# Sheet2.net
KiCad netlist of a schematic drawn in Altium Designer
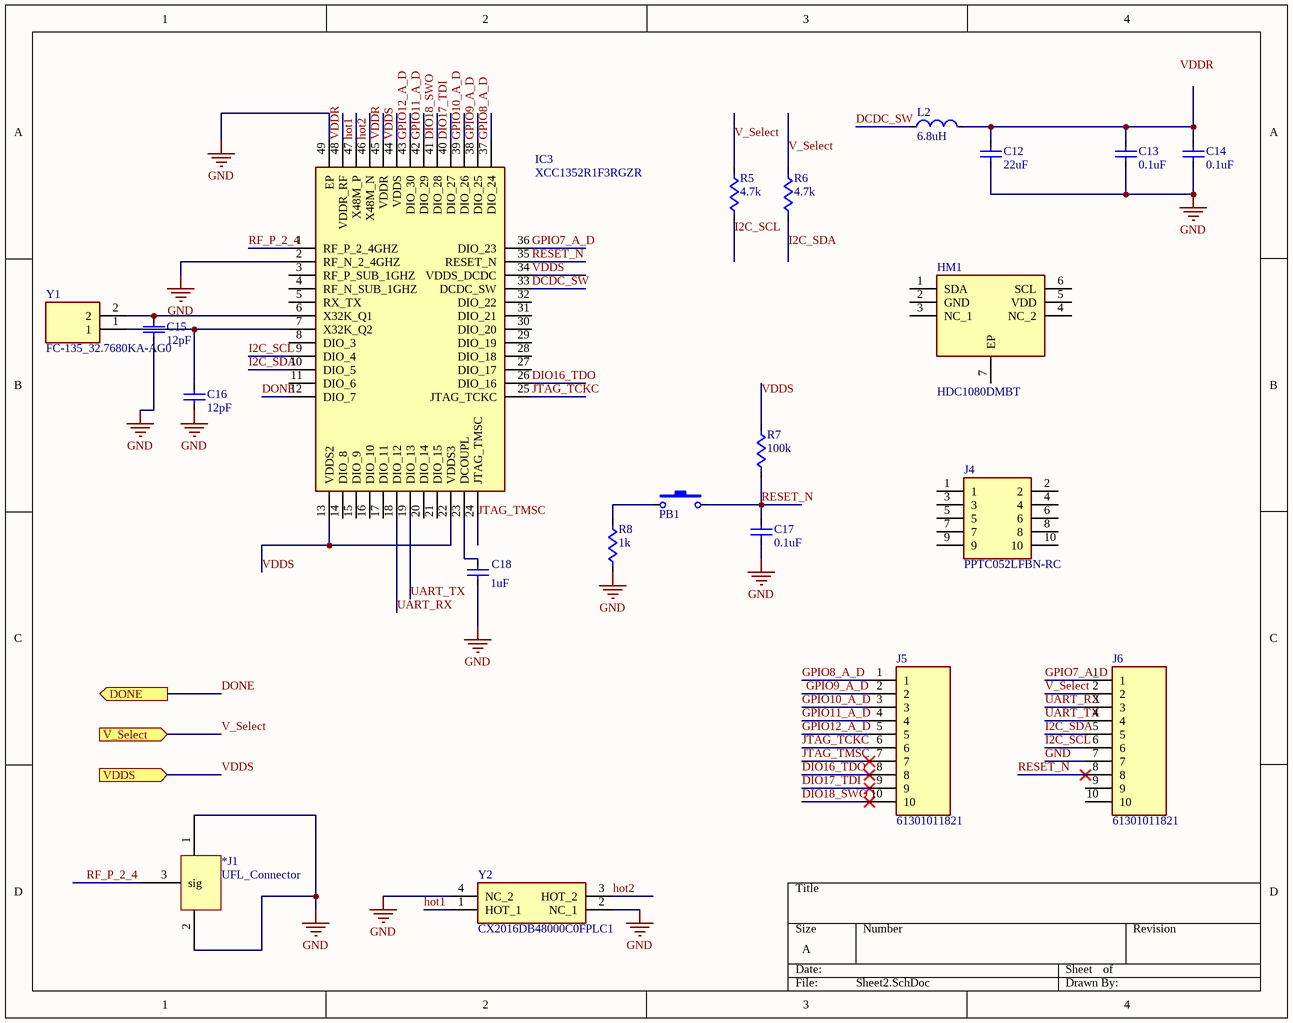
[diagram p0: Sheet2.SchDoc]

(export (version "E")
  (design (tool "Eeschema 10.0.6"))
  (components
    (comp (ref "*J1")
      (value "UFL_Connector")
      (footprint "UFL_Connector")
      (description "CONN U.FL RCPT STR 50 OHM SMD")
      (libsource (lib "Enviornmental_Sensor") (part "UFL_Connector"))
    )
    (comp (ref "C12")
      (value "22uF")
      (footprint "PASSIVE-CAPACITOR-0603")
      (description "Generic Capacitor")
      (libsource (lib "") (part "Passive-Capacitor (Generic)_1"))
    )
    (comp (ref "C13")
      (value "0.1uF")
      (footprint "PASSIVE-CAPACITOR-0603")
      (description "Generic Capacitor")
      (fields (field (name "Comment") "Passive-Capacitor (Generic)"))
      (libsource (lib "MasterLib") (part "Passive-Capacitor (Generic)"))
    )
    (comp (ref "C14")
      (value "0.1uF")
      (footprint "PASSIVE-CAPACITOR-0603")
      (description "Generic Capacitor")
      (fields (field (name "Comment") "Passive-Capacitor (Generic)"))
      (libsource (lib "MasterLib") (part "Passive-Capacitor (Generic)"))
    )
    (comp (ref "C15")
      (value "12pF")
      (footprint "PASSIVE-CAPACITOR-0603")
      (description "Generic Capacitor")
      (fields (field (name "Comment") "Passive-Capacitor (Generic)"))
      (libsource (lib "MasterLib") (part "Passive-Capacitor (Generic)"))
    )
    (comp (ref "C16")
      (value "12pF")
      (footprint "PASSIVE-CAPACITOR-0603")
      (description "Generic Capacitor")
      (fields (field (name "Comment") "Passive-Capacitor (Generic)"))
      (libsource (lib "MasterLib") (part "Passive-Capacitor (Generic)"))
    )
    (comp (ref "C17")
      (value "0.1uF")
      (footprint "PASSIVE-CAPACITOR-0603")
      (description "Generic Capacitor")
      (fields (field (name "Comment") "Passive-Capacitor (Generic)"))
      (libsource (lib "MasterLib") (part "Passive-Capacitor (Generic)"))
    )
    (comp (ref "C18")
      (value "1uF")
      (footprint "PASSIVE-CAPACITOR-0603")
      (description "Generic Capacitor")
      (fields (field (name "Comment") "Passive-Capacitor (Generic)"))
      (libsource (lib "MasterLib") (part "Passive-Capacitor (Generic)"))
    )
    (comp (ref "HM1")
      (value "HDC1080DMBT")
      (footprint "SON100P300X300X80-7N")
      (description "Hygrometer")
      (fields
        (field (name "MOUSER PART NUMBER") "595-HDC1080DMBT")
        (field (name "RS PART NUMBER") "1330170P")
      )
      (libsource (lib "Enviornmental_Sensor") (part "HDC1080DMBT"))
    )
    (comp (ref "IC3")
      (value "XCC1352R1F3RGZR")
      (footprint "QFN50P700X700X100-49N-D")
      (description "Integrated Circuit")
      (libsource (lib "Enviornmental_Sensor") (part "XCC1352R1F3RGZR"))
    )
    (comp (ref "J4")
      (value "PPTC052LFBN-RC")
      (footprint "SHDR10W87P254_2X5_1320X508X870P")
      (description "Connector")
      (libsource (lib "Enviornmental_Sensor") (part "PPTC052LFBN-RC"))
    )
    (comp (ref "J5")
      (value "61301011821")
      (footprint "SHDR10W87P0X254_1X10_2590X250X865P")
      (description "Connector")
      (fields (field (name "MOUSER PART NUMBER") "710-61301011821"))
      (libsource (lib "Enviornmental_Sensor") (part "61301011821"))
    )
    (comp (ref "J6")
      (value "61301011821")
      (footprint "SHDR10W87P0X254_1X10_2590X250X865P")
      (description "Connector")
      (fields (field (name "MOUSER PART NUMBER") "710-61301011821"))
      (libsource (lib "Enviornmental_Sensor") (part "61301011821"))
    )
    (comp (ref "L2")
      (value "6.8uH")
      (footprint "PASSIVE-INDUCTOR-0603")
      (description "Generic Inductor")
      (fields (field (name "Comment") "Passive-Inductor (Generic)"))
      (libsource (lib "MasterLib") (part "Passive-Inductor (Generic)"))
    )
    (comp (ref "PB1")
      (value "Interface-Push-Button")
      (footprint "INTERFACE-PUSH-BUTTON")
      (description "2.5mm Tall, 2.5N Force, Straight, SMD, Push Button")
      (fields
        (field (name "MANUFACTURER") "C&K Components")
        (field (name "MANUFACTURER PART NUMBER") "PTS820 J25K SMTR LFS")
      )
      (libsource (lib "MasterLib") (part "Interface-Push-Button"))
    )
    (comp (ref "R5")
      (value "4.7k")
      (footprint "PASSIVE-RESISTOR-0603")
      (description "Generic Resistor")
      (fields (field (name "Comment") "Passive-Resistor (Generic)"))
      (libsource (lib "MasterLib") (part "Passive-Resistor (Generic)"))
    )
    (comp (ref "R6")
      (value "4.7k")
      (footprint "PASSIVE-RESISTOR-0603")
      (description "Generic Resistor")
      (fields (field (name "Comment") "Passive-Resistor (Generic)"))
      (libsource (lib "MasterLib") (part "Passive-Resistor (Generic)"))
    )
    (comp (ref "R7")
      (value "100k")
      (footprint "PASSIVE-RESISTOR-0603")
      (description "Generic Resistor")
      (fields (field (name "Comment") "Passive-Resistor (Generic)"))
      (libsource (lib "MasterLib") (part "Passive-Resistor (Generic)"))
    )
    (comp (ref "R8")
      (value "1k")
      (footprint "PASSIVE-RESISTOR-0603")
      (description "Generic Resistor")
      (fields (field (name "Comment") "Passive-Resistor (Generic)"))
      (libsource (lib "MasterLib") (part "Passive-Resistor (Generic)"))
    )
    (comp (ref "Y1")
      (value "FC-135_32.7680KA-AG0")
      (footprint "FC135327680KAAG0")
      (description "Crystal or Oscillator")
      (fields
        (field (name "MANUFACTURER_PART_NUMBER") "FC-135 32.7680KA-AG0")
        (field (name "MOUSER PART NUMBER") "732-FC135-32.76KAAG0")
      )
      (libsource (lib "Enviornmental_Sensor") (part "FC-135_32.7680KA-AG0"))
    )
    (comp (ref "Y2")
      (value "CX2016DB48000C0FPLC1")
      (footprint "CX2016DB48000C0FPLC1")
      (description "Crystal or Oscillator")
      (fields (field (name "MOUSER PART NUMBER") "581-CX2016DB48CFPLC1"))
      (libsource (lib "Enviornmental_Sensor") (part "CX2016DB48000C0FPLC1"))
    )
  )
  (nets
    (net (code "1") (name "/DCDC_SW") (class "Default")
      (node (ref "IC3") (pin "33") (pinfunction "DCDC_SW_33") (pintype "passive"))
      (node (ref "L2") (pin "1") (pinfunction "1_1") (pintype "passive"))
    )
    (net (code "2") (name "/DIO16_TDO") (class "Default")
      (node (ref "IC3") (pin "26") (pinfunction "DIO_16_26") (pintype "passive"))
      (node (ref "J5") (pin "8") (pinfunction "8_8") (pintype "passive"))
    )
    (net (code "3") (name "/DIO17_TDI") (class "Default")
      (node (ref "IC3") (pin "40") (pinfunction "DIO_27_40") (pintype "passive"))
      (node (ref "J5") (pin "9") (pinfunction "9_9") (pintype "passive"))
    )
    (net (code "4") (name "/DIO18_SWO") (class "Default")
      (node (ref "IC3") (pin "41") (pinfunction "DIO_28_41") (pintype "passive"))
      (node (ref "J5") (pin "10") (pinfunction "10_10") (pintype "passive"))
    )
    (net (code "5") (name "/DONE") (class "Default")
      (node (ref "IC3") (pin "12") (pinfunction "DIO_7_12") (pintype "passive"))
    )
    (net (code "6") (name "/GPIO7_A_D") (class "Default")
      (node (ref "IC3") (pin "36") (pinfunction "DIO_23_36") (pintype "passive"))
      (node (ref "J6") (pin "1") (pinfunction "1_1") (pintype "passive"))
    )
    (net (code "7") (name "/GPIO8_A_D") (class "Default")
      (node (ref "IC3") (pin "37") (pinfunction "DIO_24_37") (pintype "passive"))
      (node (ref "J5") (pin "1") (pinfunction "1_1") (pintype "passive"))
    )
    (net (code "8") (name "/GPIO9_A_D") (class "Default")
      (node (ref "IC3") (pin "38") (pinfunction "DIO_25_38") (pintype "passive"))
      (node (ref "J5") (pin "2") (pinfunction "2_2") (pintype "passive"))
    )
    (net (code "9") (name "/GPIO10_A_D") (class "Default")
      (node (ref "IC3") (pin "39") (pinfunction "DIO_26_39") (pintype "passive"))
      (node (ref "J5") (pin "3") (pinfunction "3_3") (pintype "passive"))
    )
    (net (code "10") (name "/GPIO11_A_D") (class "Default")
      (node (ref "IC3") (pin "42") (pinfunction "DIO_29_42") (pintype "passive"))
      (node (ref "J5") (pin "4") (pinfunction "4_4") (pintype "passive"))
    )
    (net (code "11") (name "/GPIO12_A_D") (class "Default")
      (node (ref "IC3") (pin "43") (pinfunction "DIO_30_43") (pintype "passive"))
      (node (ref "J5") (pin "5") (pinfunction "5_5") (pintype "passive"))
    )
    (net (code "12") (name "/I2C_SCL") (class "Default")
      (node (ref "IC3") (pin "9") (pinfunction "DIO_4_9") (pintype "passive"))
      (node (ref "J6") (pin "6") (pinfunction "6_6") (pintype "passive"))
      (node (ref "R5") (pin "1") (pinfunction "1_1") (pintype "passive"))
    )
    (net (code "13") (name "/I2C_SDA") (class "Default")
      (node (ref "IC3") (pin "10") (pinfunction "DIO_5_10") (pintype "passive"))
      (node (ref "J6") (pin "5") (pinfunction "5_5") (pintype "passive"))
      (node (ref "R6") (pin "1") (pinfunction "1_1") (pintype "passive"))
    )
    (net (code "14") (name "/JTAG_TCKC") (class "Default")
      (node (ref "IC3") (pin "25") (pinfunction "JTAG_TCKC_25") (pintype "passive"))
      (node (ref "J5") (pin "6") (pinfunction "6_6") (pintype "passive"))
    )
    (net (code "15") (name "/JTAG_TMSC") (class "Default")
      (node (ref "IC3") (pin "24") (pinfunction "JTAG_TMSC_24") (pintype "passive"))
      (node (ref "J5") (pin "7") (pinfunction "7_7") (pintype "passive"))
    )
    (net (code "16") (name "/RESET_N") (class "Default")
      (node (ref "C17") (pin "1") (pinfunction "1_1") (pintype "passive"))
      (node (ref "IC3") (pin "35") (pinfunction "RESET_N_35") (pintype "passive"))
      (node (ref "J6") (pin "8") (pinfunction "8_8") (pintype "passive"))
      (node (ref "PB1") (pin "2") (pinfunction "2_2") (pintype "passive"))
      (node (ref "R7") (pin "1") (pinfunction "1_1") (pintype "passive"))
    )
    (net (code "17") (name "/RF_P_2_4") (class "Default")
      (node (ref "*J1") (pin "3") (pinfunction "sig_3") (pintype "passive"))
      (node (ref "IC3") (pin "1") (pinfunction "RF_P_2_4GHZ_1") (pintype "passive"))
    )
    (net (code "18") (name "/UART_RX") (class "Default")
      (node (ref "IC3") (pin "18") (pinfunction "DIO_12_18") (pintype "passive"))
      (node (ref "J6") (pin "3") (pinfunction "3_3") (pintype "passive"))
    )
    (net (code "19") (name "/UART_TX") (class "Default")
      (node (ref "IC3") (pin "19") (pinfunction "DIO_13_19") (pintype "passive"))
      (node (ref "J6") (pin "4") (pinfunction "4_4") (pintype "passive"))
    )
    (net (code "20") (name "/VDDR") (class "Default")
      (node (ref "IC3") (pin "45") (pinfunction "VDDR_45") (pintype "passive"))
      (node (ref "IC3") (pin "48") (pinfunction "VDDR_RF_48") (pintype "passive"))
    )
    (net (code "21") (name "/VDDS") (class "Default")
      (node (ref "IC3") (pin "13") (pinfunction "VDDS2_13") (pintype "passive"))
      (node (ref "IC3") (pin "22") (pinfunction "VDDS3_22") (pintype "passive"))
      (node (ref "IC3") (pin "34") (pinfunction "VDDS_DCDC_34") (pintype "passive"))
      (node (ref "IC3") (pin "44") (pinfunction "VDDS_44") (pintype "passive"))
      (node (ref "R7") (pin "2") (pinfunction "2_2") (pintype "passive"))
    )
    (net (code "22") (name "/V_Select") (class "Default")
      (node (ref "J6") (pin "2") (pinfunction "2_2") (pintype "passive"))
      (node (ref "R5") (pin "2") (pinfunction "2_2") (pintype "passive"))
      (node (ref "R6") (pin "2") (pinfunction "2_2") (pintype "passive"))
    )
    (net (code "23") (name "/hot1") (class "Default")
      (node (ref "IC3") (pin "47") (pinfunction "X48M_P_47") (pintype "passive"))
      (node (ref "Y2") (pin "1") (pinfunction "HOT_1_1") (pintype "passive"))
    )
    (net (code "24") (name "/hot2") (class "Default")
      (node (ref "IC3") (pin "46") (pinfunction "X48M_N_46") (pintype "passive"))
      (node (ref "Y2") (pin "3") (pinfunction "HOT_2_3") (pintype "passive"))
    )
    (net (code "25") (name "GND") (class "Default")
      (node (ref "*J1") (pin "1") (pinfunction "12_1") (pintype "passive"))
      (node (ref "*J1") (pin "2") (pinfunction "14_2") (pintype "passive"))
      (node (ref "C12") (pin "2") (pinfunction "2_2") (pintype "passive"))
      (node (ref "C13") (pin "1") (pinfunction "1_1") (pintype "passive"))
      (node (ref "C14") (pin "1") (pinfunction "1_1") (pintype "passive"))
      (node (ref "C15") (pin "1") (pinfunction "1_1") (pintype "passive"))
      (node (ref "C16") (pin "1") (pinfunction "1_1") (pintype "passive"))
      (node (ref "C17") (pin "2") (pinfunction "2_2") (pintype "passive"))
      (node (ref "C18") (pin "1") (pinfunction "1_1") (pintype "passive"))
      (node (ref "IC3") (pin "2") (pinfunction "RF_N_2_4GHZ_2") (pintype "passive"))
      (node (ref "IC3") (pin "49") (pinfunction "EP_49") (pintype "passive"))
      (node (ref "J6") (pin "7") (pinfunction "7_7") (pintype "passive"))
      (node (ref "R8") (pin "1") (pinfunction "1_1") (pintype "passive"))
      (node (ref "Y2") (pin "2") (pinfunction "NC_1_2") (pintype "passive"))
      (node (ref "Y2") (pin "4") (pinfunction "NC_2_4") (pintype "passive"))
    )
    (net (code "26") (name "Net-(C12-Pad1)") (class "Default")
      (node (ref "C12") (pin "1") (pinfunction "1_1") (pintype "passive"))
      (node (ref "C13") (pin "2") (pinfunction "2_2") (pintype "passive"))
      (node (ref "C14") (pin "2") (pinfunction "2_2") (pintype "passive"))
      (node (ref "L2") (pin "2") (pinfunction "2_2") (pintype "passive"))
    )
    (net (code "27") (name "Net-(IC3-DCOUPL)") (class "Default")
      (node (ref "C18") (pin "2") (pinfunction "2_2") (pintype "passive"))
      (node (ref "IC3") (pin "23") (pinfunction "DCOUPL_23") (pintype "passive"))
    )
    (net (code "28") (name "Net-(IC3-X32K_Q1)") (class "Default")
      (node (ref "C15") (pin "2") (pinfunction "2_2") (pintype "passive"))
      (node (ref "IC3") (pin "6") (pinfunction "X32K_Q1_6") (pintype "passive"))
      (node (ref "Y1") (pin "2") (pinfunction "2_2") (pintype "passive"))
    )
    (net (code "29") (name "Net-(IC3-X32K_Q2)") (class "Default")
      (node (ref "C16") (pin "2") (pinfunction "2_2") (pintype "passive"))
      (node (ref "IC3") (pin "7") (pinfunction "X32K_Q2_7") (pintype "passive"))
      (node (ref "Y1") (pin "1") (pinfunction "1_1") (pintype "passive"))
    )
    (net (code "30") (name "Net-(PB1-Pad1)") (class "Default")
      (node (ref "PB1") (pin "1") (pinfunction "1_1") (pintype "passive"))
      (node (ref "R8") (pin "2") (pinfunction "2_2") (pintype "passive"))
    )
    (net (code "31") (name "unconnected-(HM1-EP-Pad7)") (class "Default")
      (node (ref "HM1") (pin "7") (pinfunction "EP_7") (pintype "power_in"))
    )
    (net (code "32") (name "unconnected-(HM1-GND-Pad2)") (class "Default")
      (node (ref "HM1") (pin "2") (pinfunction "GND_2") (pintype "power_in"))
    )
    (net (code "33") (name "unconnected-(HM1-NC_1-Pad3)") (class "Default")
      (node (ref "HM1") (pin "3") (pinfunction "NC_1_3") (pintype "passive"))
    )
    (net (code "34") (name "unconnected-(HM1-NC_2-Pad4)") (class "Default")
      (node (ref "HM1") (pin "4") (pinfunction "NC_2_4") (pintype "passive"))
    )
    (net (code "35") (name "unconnected-(HM1-SCL-Pad6)") (class "Default")
      (node (ref "HM1") (pin "6") (pinfunction "SCL_6") (pintype "passive"))
    )
    (net (code "36") (name "unconnected-(HM1-SDA-Pad1)") (class "Default")
      (node (ref "HM1") (pin "1") (pinfunction "SDA_1") (pintype "passive"))
    )
    (net (code "37") (name "unconnected-(HM1-VDD-Pad5)") (class "Default")
      (node (ref "HM1") (pin "5") (pinfunction "VDD_5") (pintype "power_in"))
    )
    (net (code "38") (name "unconnected-(IC3-DIO_3-Pad8)") (class "Default")
      (node (ref "IC3") (pin "8") (pinfunction "DIO_3_8") (pintype "passive"))
    )
    (net (code "39") (name "unconnected-(IC3-DIO_6-Pad11)") (class "Default")
      (node (ref "IC3") (pin "11") (pinfunction "DIO_6_11") (pintype "passive"))
    )
    (net (code "40") (name "unconnected-(IC3-DIO_8-Pad14)") (class "Default")
      (node (ref "IC3") (pin "14") (pinfunction "DIO_8_14") (pintype "passive"))
    )
    (net (code "41") (name "unconnected-(IC3-DIO_9-Pad15)") (class "Default")
      (node (ref "IC3") (pin "15") (pinfunction "DIO_9_15") (pintype "passive"))
    )
    (net (code "42") (name "unconnected-(IC3-DIO_10-Pad16)") (class "Default")
      (node (ref "IC3") (pin "16") (pinfunction "DIO_10_16") (pintype "passive"))
    )
    (net (code "43") (name "unconnected-(IC3-DIO_11-Pad17)") (class "Default")
      (node (ref "IC3") (pin "17") (pinfunction "DIO_11_17") (pintype "passive"))
    )
    (net (code "44") (name "unconnected-(IC3-DIO_14-Pad20)") (class "Default")
      (node (ref "IC3") (pin "20") (pinfunction "DIO_14_20") (pintype "passive"))
    )
    (net (code "45") (name "unconnected-(IC3-DIO_15-Pad21)") (class "Default")
      (node (ref "IC3") (pin "21") (pinfunction "DIO_15_21") (pintype "passive"))
    )
    (net (code "46") (name "unconnected-(IC3-DIO_17-Pad27)") (class "Default")
      (node (ref "IC3") (pin "27") (pinfunction "DIO_17_27") (pintype "passive"))
    )
    (net (code "47") (name "unconnected-(IC3-DIO_18-Pad28)") (class "Default")
      (node (ref "IC3") (pin "28") (pinfunction "DIO_18_28") (pintype "passive"))
    )
    (net (code "48") (name "unconnected-(IC3-DIO_19-Pad29)") (class "Default")
      (node (ref "IC3") (pin "29") (pinfunction "DIO_19_29") (pintype "passive"))
    )
    (net (code "49") (name "unconnected-(IC3-DIO_20-Pad30)") (class "Default")
      (node (ref "IC3") (pin "30") (pinfunction "DIO_20_30") (pintype "passive"))
    )
    (net (code "50") (name "unconnected-(IC3-DIO_21-Pad31)") (class "Default")
      (node (ref "IC3") (pin "31") (pinfunction "DIO_21_31") (pintype "passive"))
    )
    (net (code "51") (name "unconnected-(IC3-DIO_22-Pad32)") (class "Default")
      (node (ref "IC3") (pin "32") (pinfunction "DIO_22_32") (pintype "passive"))
    )
    (net (code "52") (name "unconnected-(IC3-RF_N_SUB_1GHZ-Pad4)") (class "Default")
      (node (ref "IC3") (pin "4") (pinfunction "RF_N_SUB_1GHZ_4") (pintype "passive"))
    )
    (net (code "53") (name "unconnected-(IC3-RF_P_SUB_1GHZ-Pad3)") (class "Default")
      (node (ref "IC3") (pin "3") (pinfunction "RF_P_SUB_1GHZ_3") (pintype "passive"))
    )
    (net (code "54") (name "unconnected-(IC3-RX_TX-Pad5)") (class "Default")
      (node (ref "IC3") (pin "5") (pinfunction "RX_TX_5") (pintype "passive"))
    )
    (net (code "55") (name "unconnected-(J4-Pad1)") (class "Default")
      (node (ref "J4") (pin "1") (pinfunction "1_1") (pintype "passive"))
    )
    (net (code "56") (name "unconnected-(J4-Pad2)") (class "Default")
      (node (ref "J4") (pin "2") (pinfunction "2_2") (pintype "passive"))
    )
    (net (code "57") (name "unconnected-(J4-Pad3)") (class "Default")
      (node (ref "J4") (pin "3") (pinfunction "3_3") (pintype "passive"))
    )
    (net (code "58") (name "unconnected-(J4-Pad4)") (class "Default")
      (node (ref "J4") (pin "4") (pinfunction "4_4") (pintype "passive"))
    )
    (net (code "59") (name "unconnected-(J4-Pad5)") (class "Default")
      (node (ref "J4") (pin "5") (pinfunction "5_5") (pintype "passive"))
    )
    (net (code "60") (name "unconnected-(J4-Pad6)") (class "Default")
      (node (ref "J4") (pin "6") (pinfunction "6_6") (pintype "passive"))
    )
    (net (code "61") (name "unconnected-(J4-Pad7)") (class "Default")
      (node (ref "J4") (pin "7") (pinfunction "7_7") (pintype "passive"))
    )
    (net (code "62") (name "unconnected-(J4-Pad8)") (class "Default")
      (node (ref "J4") (pin "8") (pinfunction "8_8") (pintype "passive"))
    )
    (net (code "63") (name "unconnected-(J4-Pad9)") (class "Default")
      (node (ref "J4") (pin "9") (pinfunction "9_9") (pintype "passive"))
    )
    (net (code "64") (name "unconnected-(J4-Pad10)") (class "Default")
      (node (ref "J4") (pin "10") (pinfunction "10_10") (pintype "passive"))
    )
    (net (code "65") (name "unconnected-(J6-Pad9)") (class "Default")
      (node (ref "J6") (pin "9") (pinfunction "9_9") (pintype "passive"))
    )
    (net (code "66") (name "unconnected-(J6-Pad10)") (class "Default")
      (node (ref "J6") (pin "10") (pinfunction "10_10") (pintype "passive"))
    )
  )
)
